# Grove_Pulse_Counter.net
KiCad netlist of a schematic drawn in EAGLE
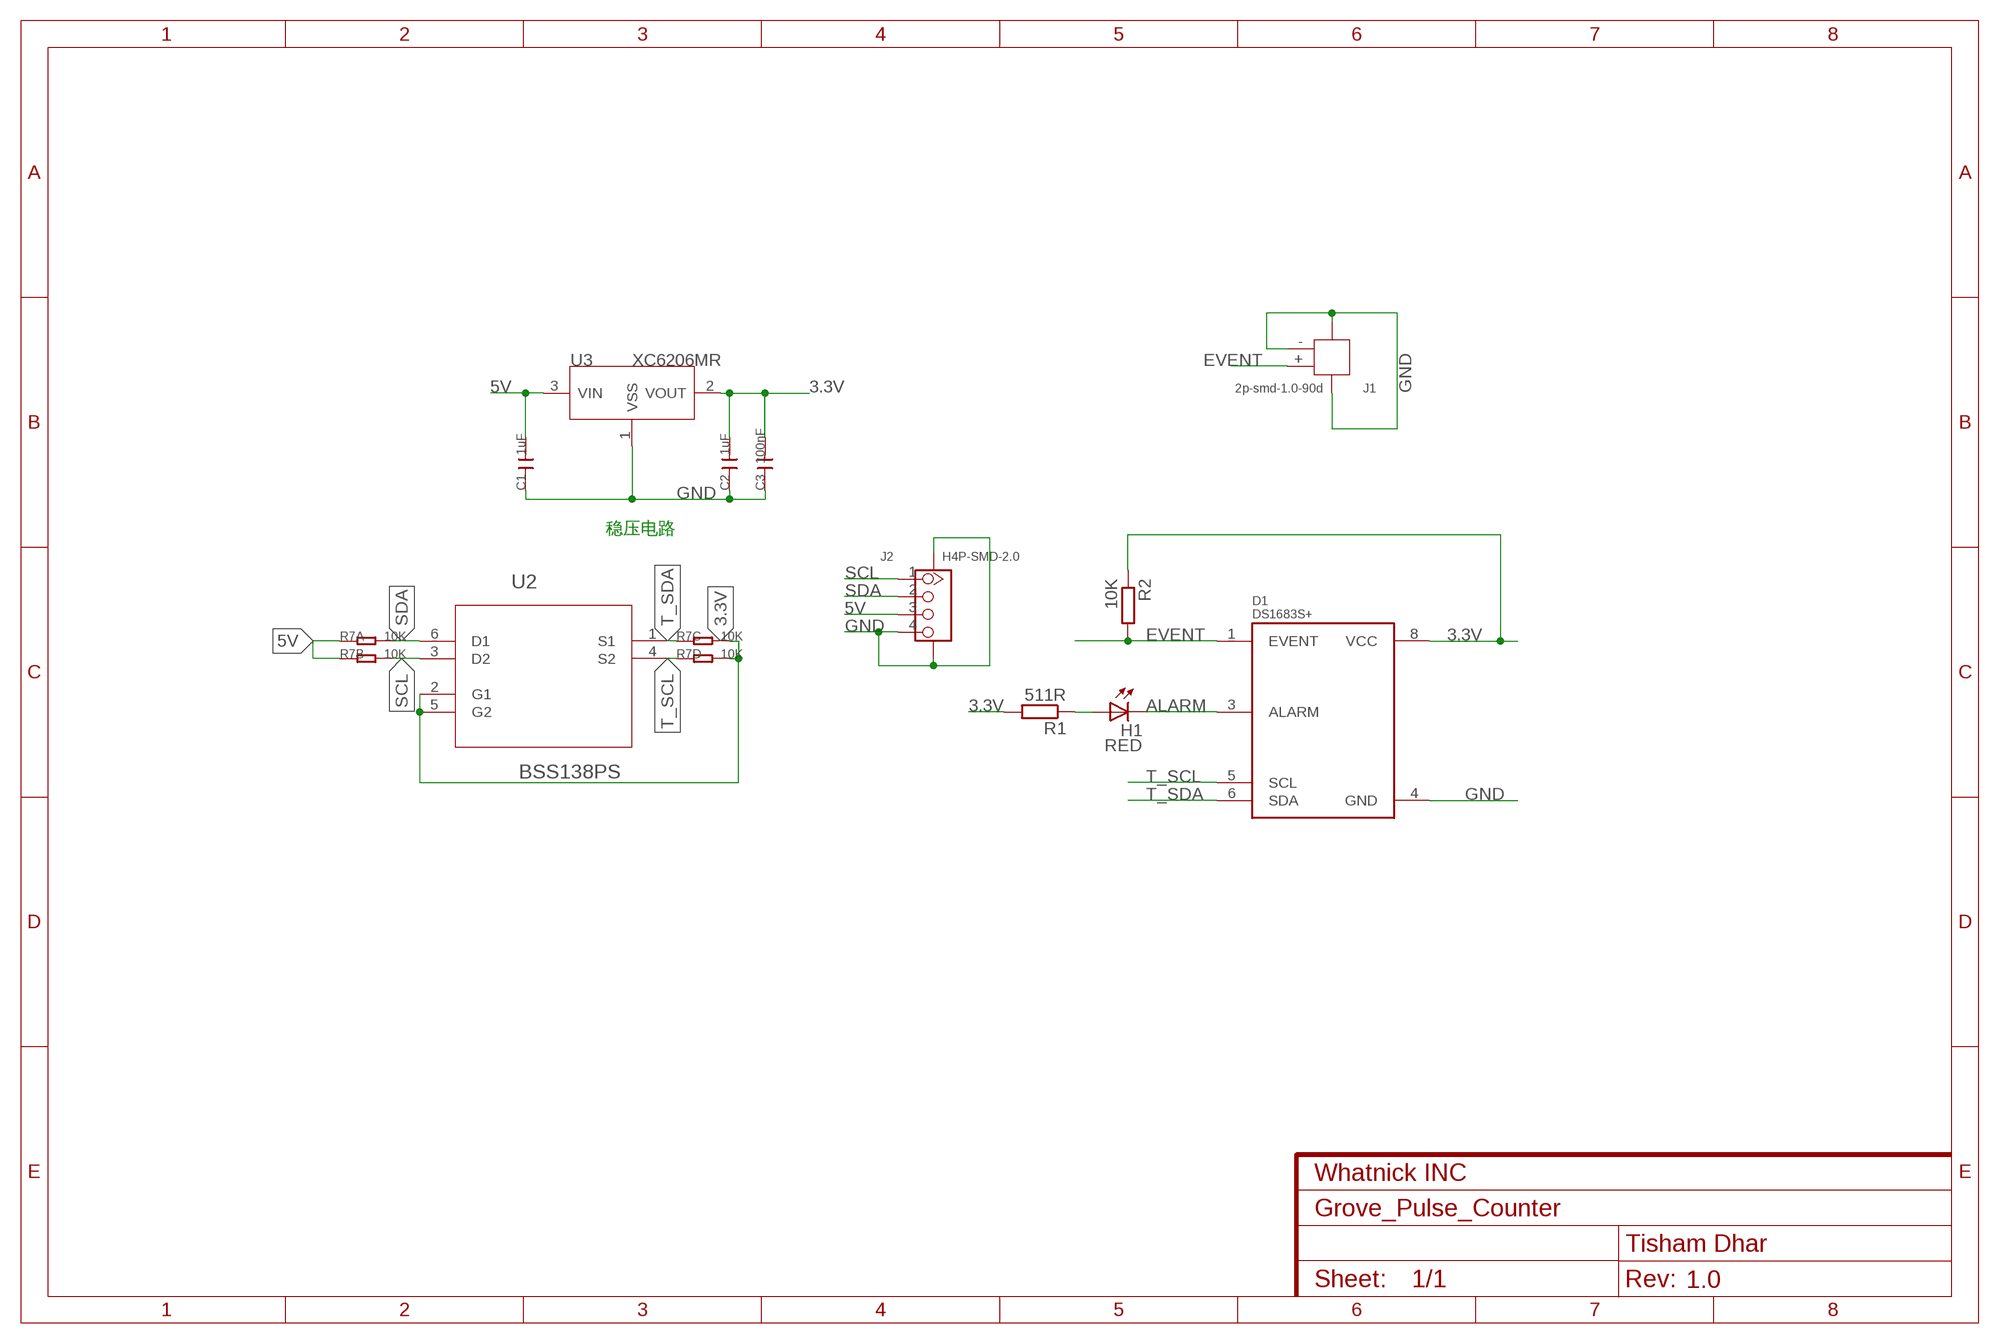
[diagram p0: schematic, sheet 1]

(export (version "E")
  (design (tool "Eeschema 10.0.6"))
  (components
    (comp (ref "C1")
      (value "1uF")
      (footprint "eagle-import:C0603")
      (libsource (lib "eagle-import") (part "C-0603"))
    )
    (comp (ref "C2")
      (value "1uF")
      (footprint "eagle-import:C0603")
      (libsource (lib "eagle-import") (part "C-0603"))
    )
    (comp (ref "C3")
      (value "100nF")
      (footprint "eagle-import:C0603")
      (libsource (lib "eagle-import") (part "C-0603"))
    )
    (comp (ref "D1")
      (value "DS1683S+")
      (footprint "eagle-import:SOIC8-N_MC")
      (libsource (lib "eagle-import") (part "DS1683S+"))
    )
    (comp (ref "H1")
      (value "RED")
      (footprint "eagle-import:CHIPLED_0603")
      (libsource (lib "eagle-import") (part "LEDCHIPLED_0603"))
    )
    (comp (ref "J1")
      (value "2p-smd-1.0-90d")
      (footprint "eagle-import:HW2-SMD-1.0-90D")
      (libsource (lib "eagle-import") (part "SMD-JST-2P-1.0-90D"))
    )
    (comp (ref "J2")
      (value "H4P-SMD-2.0")
      (footprint "eagle-import:HW4-SMD-2.0")
      (libsource (lib "eagle-import") (part "GROVE-CONNECTOR-SMD(4+2P-2.0)"))
    )
    (comp (ref "R1")
      (value "511R")
      (footprint "eagle-import:R0603")
      (libsource (lib "eagle-import") (part "R-EU_R0603"))
    )
    (comp (ref "R2")
      (value "10K")
      (footprint "eagle-import:R0603")
      (libsource (lib "eagle-import") (part "R-EU_R0603"))
    )
    (comp (ref "R7")
      (value "10K")
      (footprint "eagle-import:1206-8-3.3X2.4")
      (libsource (lib "eagle-import") (part "R-4R-1206"))
    )
    (comp (ref "U2")
      (value "BSS138PS")
      (footprint "eagle-import:SOT65P210X110-6N")
      (libsource (lib "eagle-import") (part "BSS138PS"))
    )
    (comp (ref "U3")
      (value "XC6206MR")
      (footprint "eagle-import:SOT23")
      (libsource (lib "eagle-import") (part "XC6206MR"))
    )
  )
  (nets
    (net (code "1") (name "/ALARM") (class "Default")
      (node (ref "D1") (pin "3") (pinfunction "ALARM_3") (pintype "bidirectional"))
      (node (ref "H1") (pin "C") (pinfunction "C_C") (pintype "passive"))
    )
    (net (code "2") (name "/EVENT") (class "Default")
      (node (ref "D1") (pin "1") (pinfunction "EVENT_1") (pintype "bidirectional"))
      (node (ref "J1") (pin "+") (pinfunction "1_+") (pintype "bidirectional"))
      (node (ref "R2") (pin "2") (pinfunction "2_2") (pintype "passive"))
    )
    (net (code "3") (name "/GND") (class "Default")
      (node (ref "C1") (pin "1") (pinfunction "1_1") (pintype "passive"))
      (node (ref "C2") (pin "1") (pinfunction "1_1") (pintype "passive"))
      (node (ref "C3") (pin "1") (pinfunction "1_1") (pintype "passive"))
      (node (ref "D1") (pin "4") (pinfunction "GND_4") (pintype "bidirectional"))
      (node (ref "J1") (pin "-") (pinfunction "2_-") (pintype "bidirectional"))
      (node (ref "J1") (pin "3") (pinfunction "3_3") (pintype "bidirectional"))
      (node (ref "J1") (pin "4") (pinfunction "4_4") (pintype "bidirectional"))
      (node (ref "J2") (pin "4") (pinfunction "4_4") (pintype "bidirectional"))
      (node (ref "J2") (pin "SS1") (pinfunction "SS1_SS1") (pintype "bidirectional"))
      (node (ref "J2") (pin "SS2") (pinfunction "SS2_SS2") (pintype "bidirectional"))
      (node (ref "U3") (pin "1") (pinfunction "VSS_1") (pintype "power_in"))
    )
    (net (code "4") (name "3.3V") (class "Default")
      (node (ref "C2") (pin "2") (pinfunction "2_2") (pintype "passive"))
      (node (ref "C3") (pin "2") (pinfunction "2_2") (pintype "passive"))
      (node (ref "D1") (pin "8") (pinfunction "VCC_8") (pintype "bidirectional"))
      (node (ref "R1") (pin "2") (pinfunction "2_2") (pintype "passive"))
      (node (ref "R2") (pin "1") (pinfunction "1_1") (pintype "passive"))
      (node (ref "R7") (pin "5") (pinfunction "2_5") (pintype "passive"))
      (node (ref "R7") (pin "6") (pinfunction "2_6") (pintype "passive"))
      (node (ref "U2") (pin "2") (pinfunction "G1_2") (pintype "input"))
      (node (ref "U2") (pin "5") (pinfunction "G2_5") (pintype "input"))
      (node (ref "U3") (pin "2") (pinfunction "VOUT_2") (pintype "output"))
    )
    (net (code "5") (name "5V") (class "Default")
      (node (ref "C1") (pin "2") (pinfunction "2_2") (pintype "passive"))
      (node (ref "J2") (pin "3") (pinfunction "3_3") (pintype "bidirectional"))
      (node (ref "R7") (pin "1") (pinfunction "1_1") (pintype "passive"))
      (node (ref "R7") (pin "2") (pinfunction "1_2") (pintype "passive"))
      (node (ref "U3") (pin "3") (pinfunction "VIN_3") (pintype "input"))
    )
    (net (code "6") (name "Net-(H1-PadA)") (class "Default")
      (node (ref "H1") (pin "A") (pinfunction "A_A") (pintype "passive"))
      (node (ref "R1") (pin "1") (pinfunction "1_1") (pintype "passive"))
    )
    (net (code "7") (name "SCL") (class "Default")
      (node (ref "J2") (pin "1") (pinfunction "1_1") (pintype "bidirectional"))
      (node (ref "R7") (pin "7") (pinfunction "2_7") (pintype "passive"))
      (node (ref "U2") (pin "3") (pinfunction "D2_3") (pintype "input"))
    )
    (net (code "8") (name "SDA") (class "Default")
      (node (ref "J2") (pin "2") (pinfunction "2_2") (pintype "bidirectional"))
      (node (ref "R7") (pin "8") (pinfunction "2_8") (pintype "passive"))
      (node (ref "U2") (pin "6") (pinfunction "D1_6") (pintype "input"))
    )
    (net (code "9") (name "T_SCL") (class "Default")
      (node (ref "D1") (pin "5") (pinfunction "SCL_5") (pintype "bidirectional"))
      (node (ref "R7") (pin "4") (pinfunction "1_4") (pintype "passive"))
      (node (ref "U2") (pin "4") (pinfunction "S2_4") (pintype "output"))
    )
    (net (code "10") (name "T_SDA") (class "Default")
      (node (ref "D1") (pin "6") (pinfunction "SDA_6") (pintype "bidirectional"))
      (node (ref "R7") (pin "3") (pinfunction "1_3") (pintype "passive"))
      (node (ref "U2") (pin "1") (pinfunction "S1_1") (pintype "output"))
    )
  )
)
